# PA_stage_1.net
KiCad netlist of a schematic drawn in Altium Designer
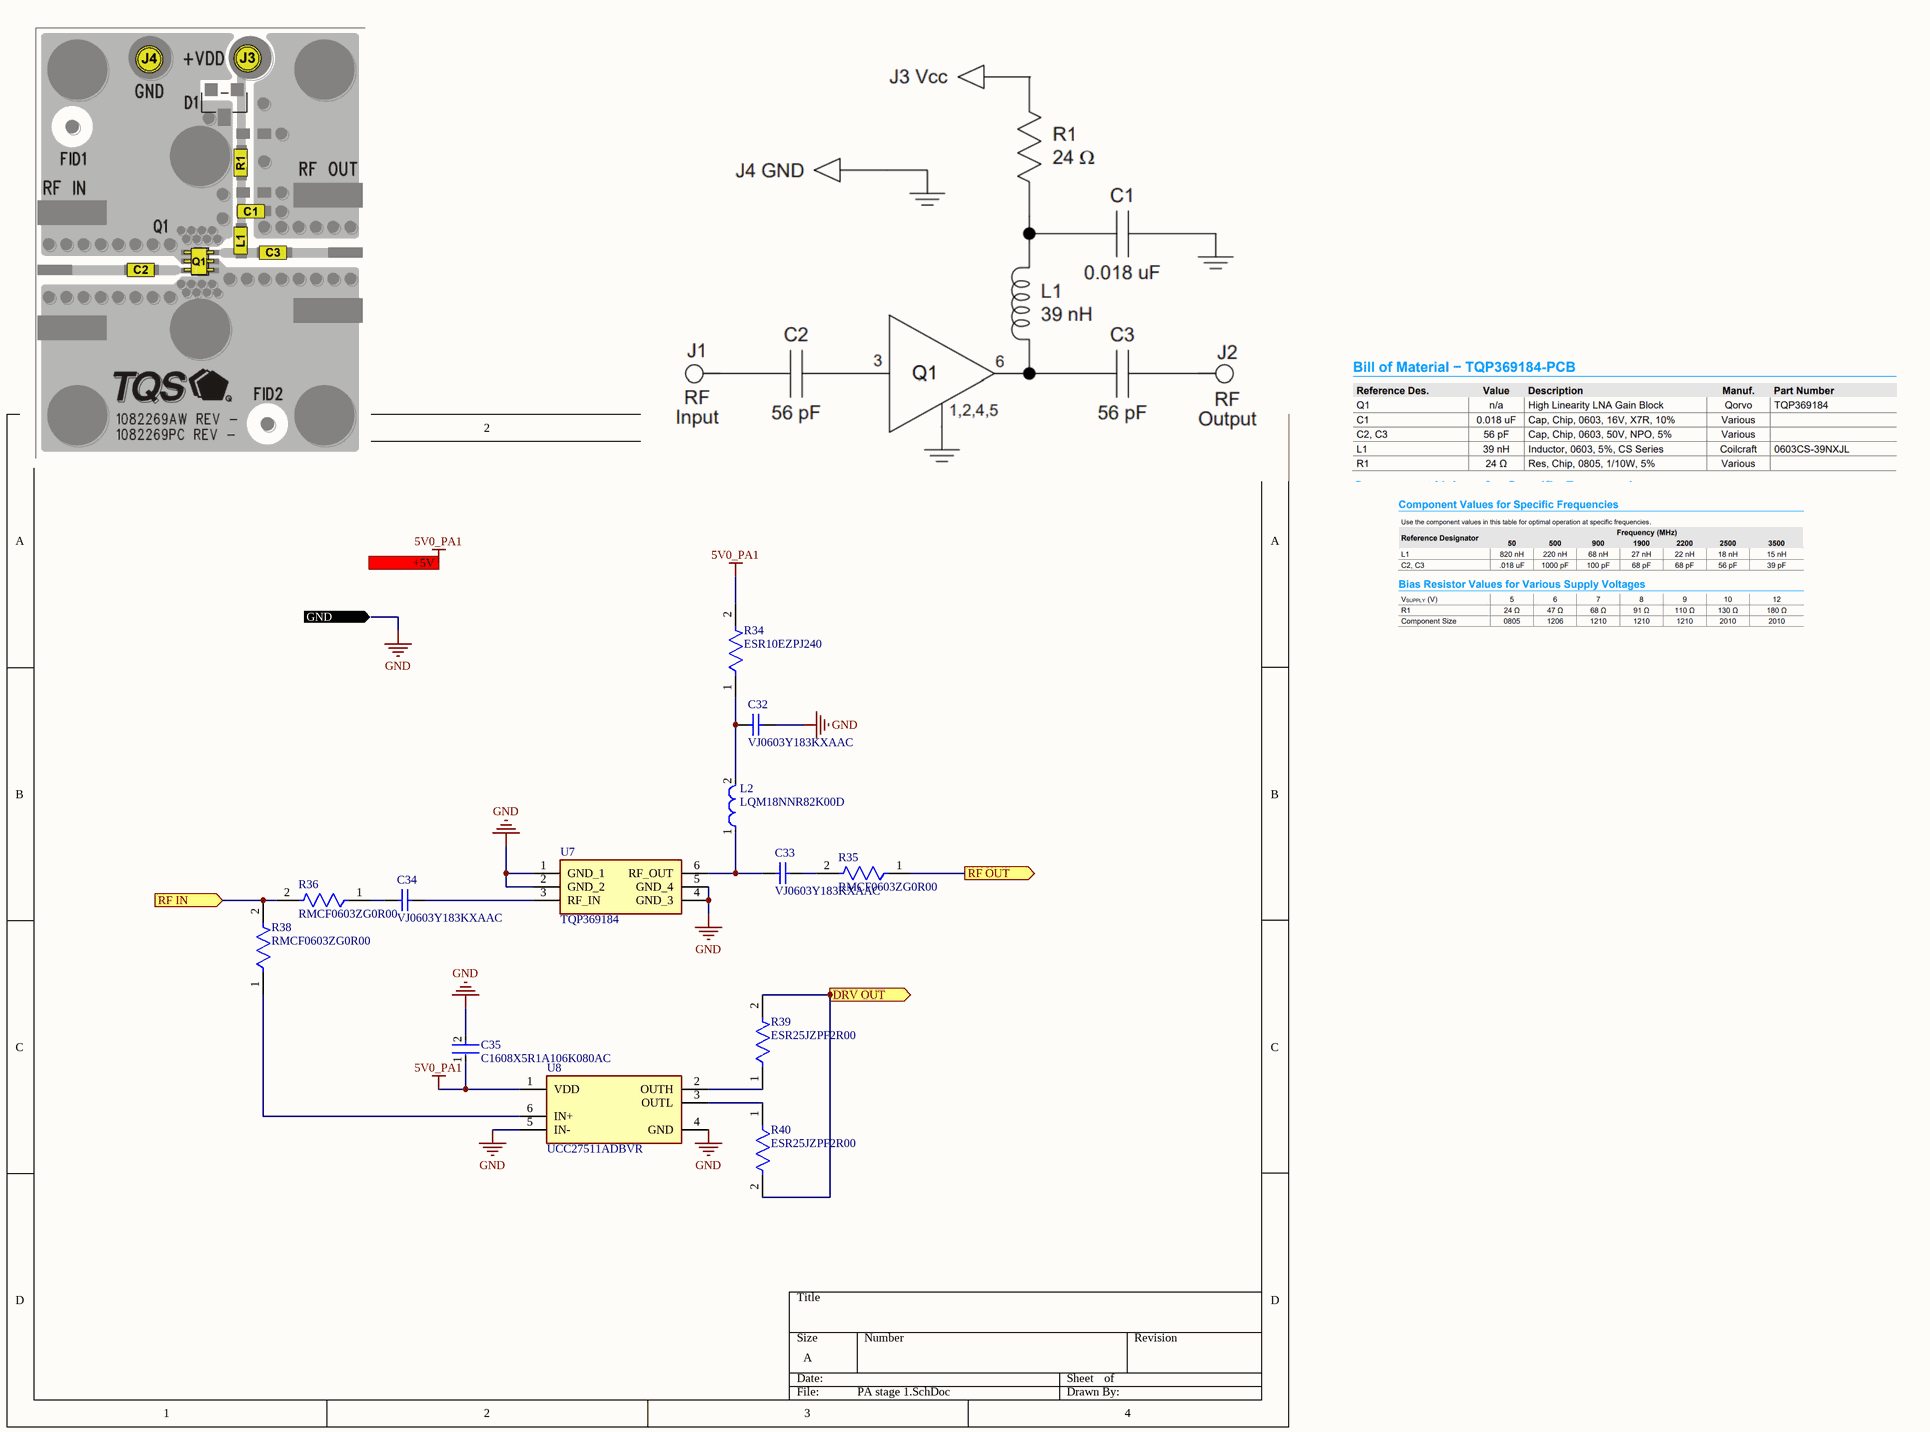
[diagram p0: PA stage 1.SchDoc]

(export (version "E")
  (design (tool "Eeschema 10.0.6"))
  (components
    (comp (ref "C32")
      (value "VJ0603Y183KXAAC")
      (footprint "CAPC1608X92X38ML15T08")
      (fields (field (name "MANUFACTURER") "Vitramon"))
      (libsource (lib "Altium Content Vault") (part "CAP"))
    )
    (comp (ref "C33")
      (value "VJ0603Y183KXAAC")
      (footprint "CAPC1608X92X38ML15T08")
      (fields (field (name "MANUFACTURER") "Vitramon"))
      (libsource (lib "Altium Content Vault") (part "CAP"))
    )
    (comp (ref "C34")
      (value "VJ0603Y183KXAAC")
      (footprint "CAPC1608X92X38ML15T08")
      (fields (field (name "MANUFACTURER") "Vitramon"))
      (libsource (lib "Altium Content Vault") (part "CAP"))
    )
    (comp (ref "C35")
      (value "C1608X5R1A106K080AC")
      (footprint "FP-C1608-080-0_1-MFG")
      (description "Multilayer Ceramic Capacitors 10μF ±10% 10V X5R SMD 0603")
      (fields (field (name "VOLTAGE") "10V") (field (name "TOLERANCE") "10%"))
      (libsource (lib "Altium Content Vault") (part "236180d848d6139a670b325ea6854c9"))
    )
    (comp (ref "L2")
      (value "LQM18NNR82K00D")
      (footprint "FP-LQM18NN_00-IPC_B")
      (description "Multilayer Type Inductor for General Circuits, 0603 (1608), 820nH, 10%, 2.1Ω, 35mA")
      (fields (field (name "TOLERANCE") "10%"))
      (libsource (lib "Altium Content Vault") (part "725321dda6339637d4d059423bc1c3c"))
    )
    (comp (ref "R34")
      (value "ESR10EZPJ240")
      (footprint "FP-ESR10-IPC_C")
      (description "24Ω ±5% 0.4W 0805 Anti-Surge Chip Resistor AEC-Q200")
      (fields (field (name "TOLERANCE") "5%"))
      (libsource (lib "Altium Content Vault") (part "1029c3af85768c4190bb7ad29bc67b5"))
    )
    (comp (ref "R35")
      (value "RMCF0603ZG0R00")
      (footprint "FP-RMCF0603-IPC_B")
      (description "0Ω ±0 0.1W 0603 Thick Film Chip Resistor AEC-Q200 compliant")
      (libsource (lib "Altium Content Vault") (part "1029c3af85768c4190bb7ad29bc67b5"))
    )
    (comp (ref "R36")
      (value "RMCF0603ZG0R00")
      (footprint "FP-RMCF0603-IPC_B")
      (description "0Ω ±0 0.1W 0603 Thick Film Chip Resistor AEC-Q200 compliant")
      (libsource (lib "Altium Content Vault") (part "1029c3af85768c4190bb7ad29bc67b5"))
    )
    (comp (ref "R38")
      (value "RMCF0603ZG0R00")
      (footprint "FP-RMCF0603-IPC_B")
      (description "0Ω ±0 0.1W 0603 Thick Film Chip Resistor AEC-Q200 compliant")
      (libsource (lib "Altium Content Vault") (part "1029c3af85768c4190bb7ad29bc67b5"))
    )
    (comp (ref "R39")
      (value "ESR25JZPF2R00")
      (footprint "FP-ESR25-MFG")
      (description "2Ω ±1% 0.66W 1210 Anti-Surge Chip Resistor AEC-Q200")
      (fields (field (name "TOLERANCE") "1%"))
      (libsource (lib "Altium Content Vault") (part "1029c3af85768c4190bb7ad29bc67b5"))
    )
    (comp (ref "R40")
      (value "ESR25JZPF2R00")
      (footprint "FP-ESR25-MFG")
      (description "2Ω ±1% 0.66W 1210 Anti-Surge Chip Resistor AEC-Q200")
      (fields (field (name "TOLERANCE") "1%"))
      (libsource (lib "Altium Content Vault") (part "1029c3af85768c4190bb7ad29bc67b5"))
    )
    (comp (ref "U7")
      (value "TQP369184")
      (footprint "SOT65P210X110-6N")
      (description "DC  6 GHz Gain Block")
      (fields (field (name "MOUSER PART NUMBER") "772-TQP369184"))
      (libsource (lib "TQP369184") (part "TQP369184"))
    )
    (comp (ref "U8")
      (value "UCC27511ADBVR")
      (footprint "FP-DBV0006A-IPC_B")
      (description "IC GATE DRVR LOW-SIDE SOT23-6")
      (libsource (lib "Altium Content Vault") (part "9cea8d48b3c5e665674ac7ab8f980b4"))
    )
  )
  (nets
    (net (code "1") (name "/DRV OUT") (class "Default")
      (node (ref "R39") (pin "2") (pinfunction "2_2") (pintype "passive"))
      (node (ref "R40") (pin "2") (pinfunction "2_2") (pintype "passive"))
    )
    (net (code "2") (name "/RF IN") (class "Default")
      (node (ref "R36") (pin "2") (pinfunction "2_2") (pintype "passive"))
      (node (ref "R38") (pin "2") (pinfunction "2_2") (pintype "passive"))
    )
    (net (code "3") (name "/RF OUT") (class "Default")
      (node (ref "R35") (pin "1") (pinfunction "1_1") (pintype "passive"))
    )
    (net (code "4") (name "5V0_PA1") (class "Default")
      (node (ref "C35") (pin "1") (pinfunction "1_1") (pintype "passive"))
      (node (ref "R34") (pin "2") (pinfunction "2_2") (pintype "passive"))
      (node (ref "U8") (pin "1") (pinfunction "VDD_1") (pintype "power_in"))
    )
    (net (code "5") (name "GND") (class "Default")
      (node (ref "C32") (pin "2") (pinfunction "2_2") (pintype "passive"))
      (node (ref "C35") (pin "2") (pinfunction "2_2") (pintype "passive"))
      (node (ref "U7") (pin "1") (pinfunction "GND_1_1") (pintype "passive"))
      (node (ref "U7") (pin "2") (pinfunction "GND_2_2") (pintype "passive"))
      (node (ref "U7") (pin "4") (pinfunction "GND_3_4") (pintype "passive"))
      (node (ref "U7") (pin "5") (pinfunction "GND_4_5") (pintype "passive"))
      (node (ref "U8") (pin "4") (pinfunction "GND_4") (pintype "power_in"))
      (node (ref "U8") (pin "5") (pinfunction "IN-_5") (pintype "tri_state"))
    )
    (net (code "6") (name "Net-(C32-Pad1)") (class "Default")
      (node (ref "C32") (pin "1") (pinfunction "1_1") (pintype "passive"))
      (node (ref "L2") (pin "2") (pinfunction "2_2") (pintype "passive"))
      (node (ref "R34") (pin "1") (pinfunction "1_1") (pintype "passive"))
    )
    (net (code "7") (name "Net-(C33-Pad2)") (class "Default")
      (node (ref "C33") (pin "2") (pinfunction "2_2") (pintype "passive"))
      (node (ref "R35") (pin "2") (pinfunction "2_2") (pintype "passive"))
    )
    (net (code "8") (name "Net-(C34-Pad1)") (class "Default")
      (node (ref "C34") (pin "1") (pinfunction "1_1") (pintype "passive"))
      (node (ref "R36") (pin "1") (pinfunction "1_1") (pintype "passive"))
    )
    (net (code "9") (name "Net-(U7-RF_IN)") (class "Default")
      (node (ref "C34") (pin "2") (pinfunction "2_2") (pintype "passive"))
      (node (ref "U7") (pin "3") (pinfunction "RF_IN_3") (pintype "passive"))
    )
    (net (code "10") (name "Net-(U7-RF_OUT)") (class "Default")
      (node (ref "C33") (pin "1") (pinfunction "1_1") (pintype "passive"))
      (node (ref "L2") (pin "1") (pinfunction "1_1") (pintype "passive"))
      (node (ref "U7") (pin "6") (pinfunction "RF_OUT_6") (pintype "passive"))
    )
    (net (code "11") (name "Net-(U8-IN+)") (class "Default")
      (node (ref "R38") (pin "1") (pinfunction "1_1") (pintype "passive"))
      (node (ref "U8") (pin "6") (pinfunction "IN+_6") (pintype "tri_state"))
    )
    (net (code "12") (name "Net-(U8-OUTH)") (class "Default")
      (node (ref "R39") (pin "1") (pinfunction "1_1") (pintype "passive"))
      (node (ref "U8") (pin "2") (pinfunction "OUTH_2") (pintype "passive"))
    )
    (net (code "13") (name "Net-(U8-OUTL)") (class "Default")
      (node (ref "R40") (pin "1") (pinfunction "1_1") (pintype "passive"))
      (node (ref "U8") (pin "3") (pinfunction "OUTL_3") (pintype "passive"))
    )
  )
)
